# PowerBoard.net
KiCad netlist of a schematic drawn in Altium Designer
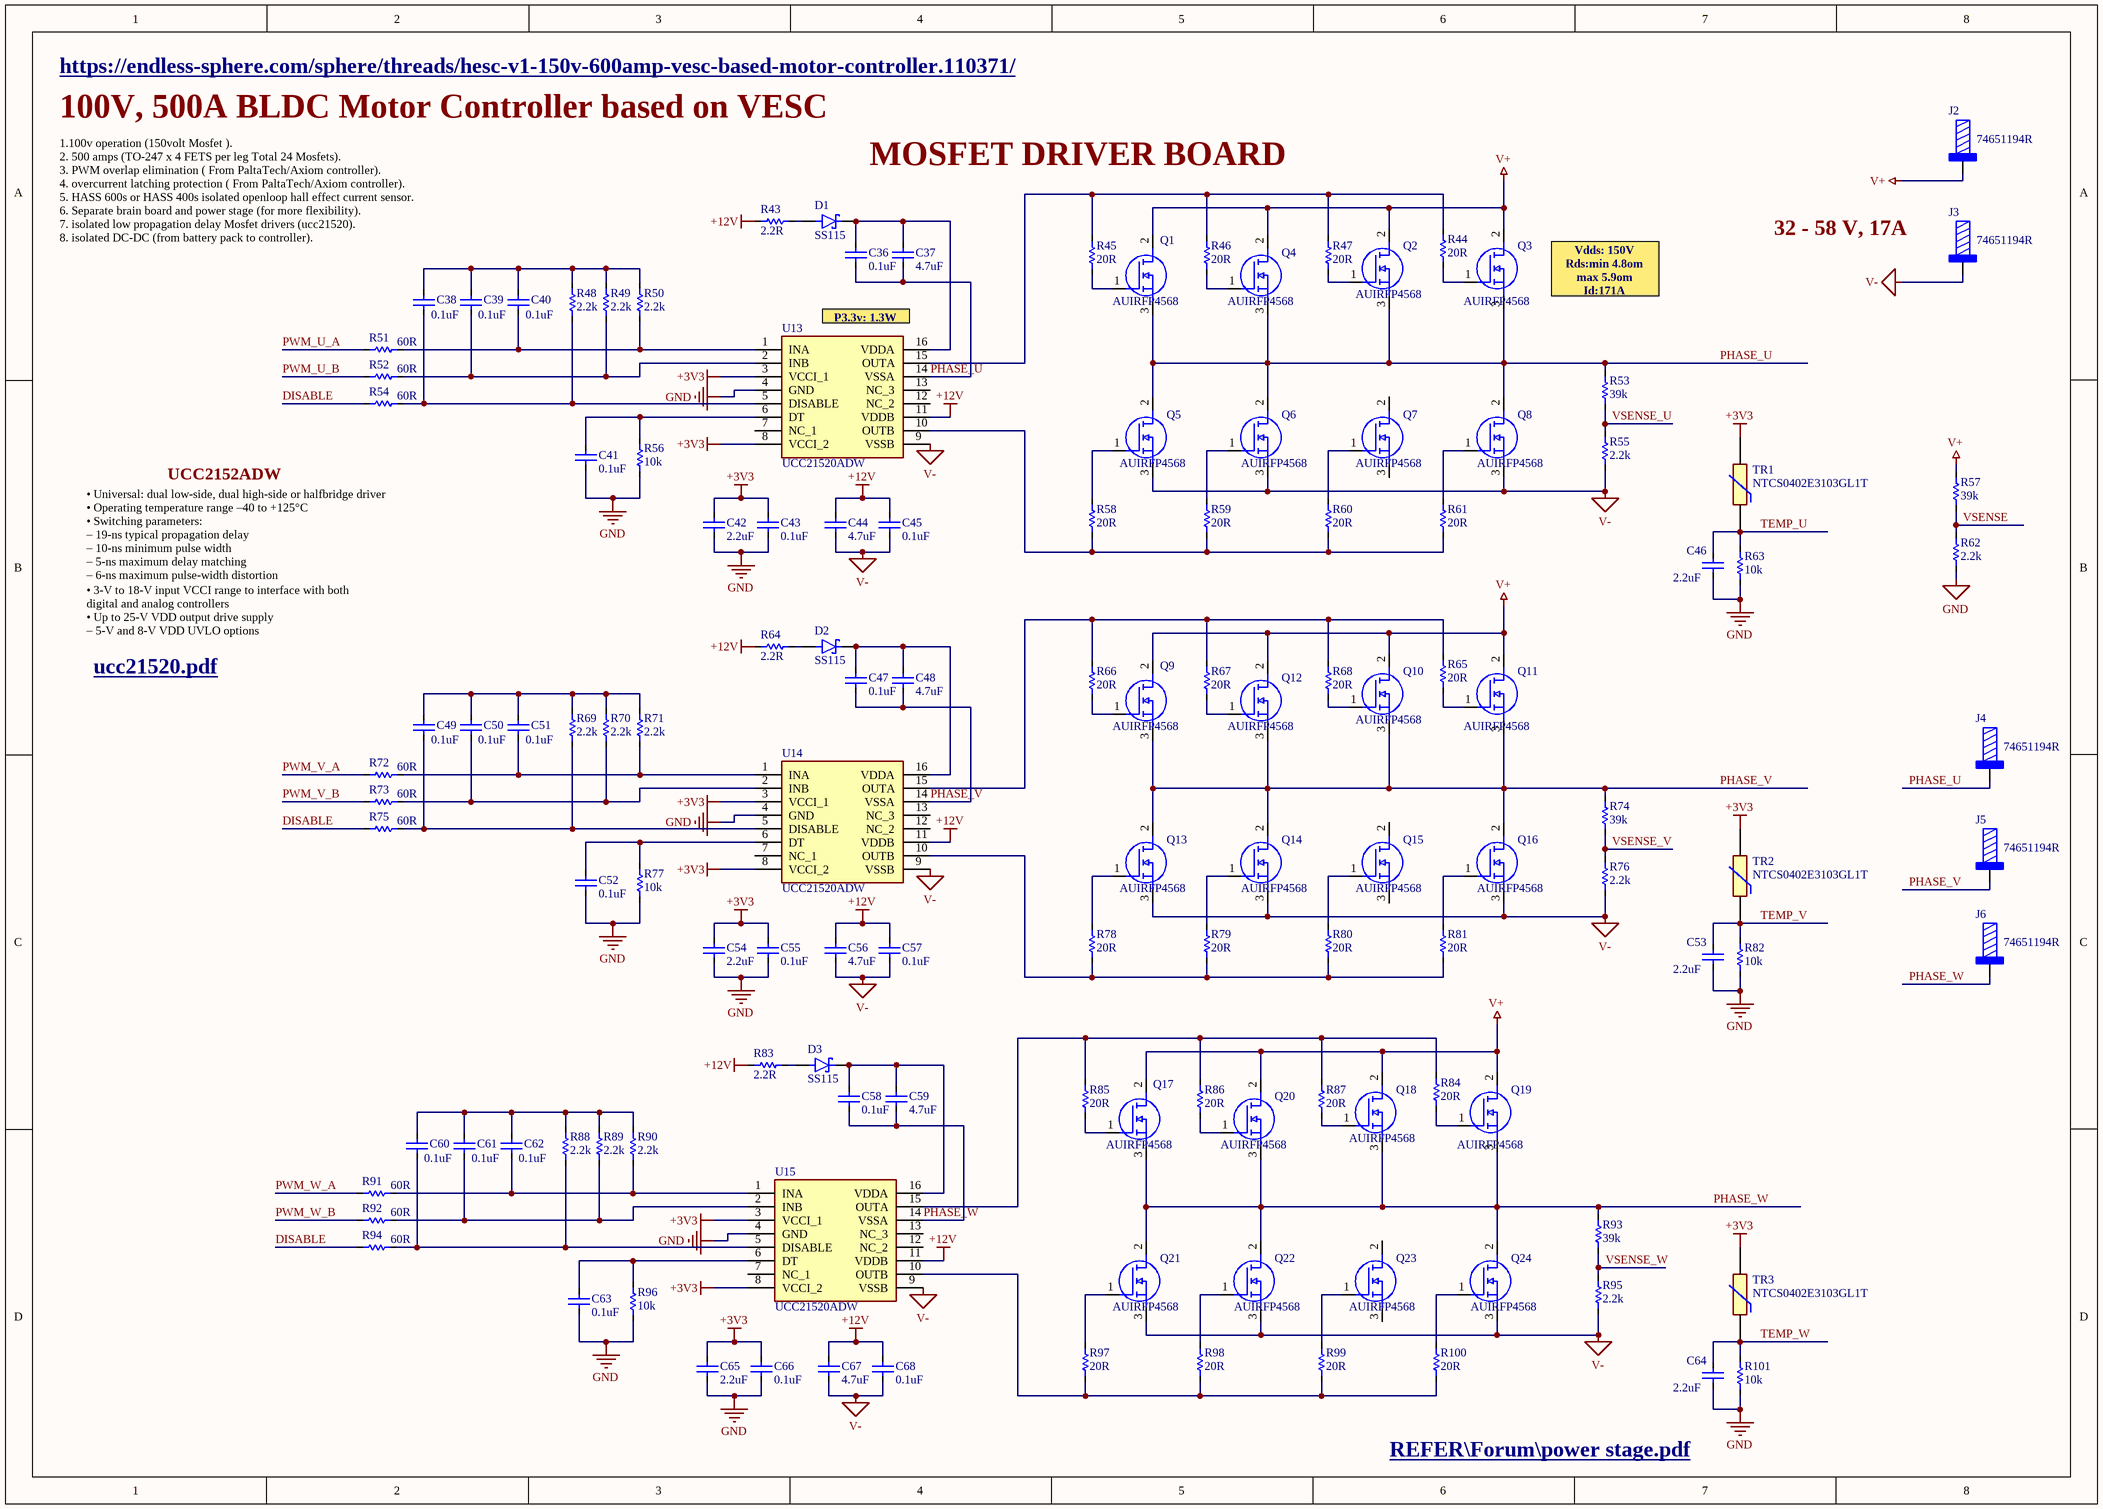
[diagram p0: PowerBoard.SchDoc]

(export (version "E")
  (design (tool "Eeschema 10.0.6"))
  (components
    (comp (ref "C36")
      (value "0.1uF")
      (footprint "SMD_C(0402)")
      (description "Multilayer Ceramic Capacitors MLCC - SMD/SMT 50 V 0.1uF X7R 0603 10%")
      (fields
        (field (name "MANUFACTURER") "Yageo")
        (field (name "MANUFACTURER PART NUMBER") "CC0603KPX7R9BB104")
      )
      (libsource (lib "CameraBoard") (part "Cap_1"))
    )
    (comp (ref "C37")
      (value "4.7uF")
      (footprint "SMD_C(0603)")
      (description "PHE840MA6100MA04R17")
      (fields
        (field (name "MANUFACTURER") "Yageo")
        (field (name "MANUFACTURER PART NUMBER") "CC0603KPX7R9BB104")
      )
      (libsource (lib "CameraBoard") (part "Cap_10"))
    )
    (comp (ref "C38")
      (value "0.1uF")
      (footprint "SMD_C(0402)")
      (description "Multilayer Ceramic Capacitors MLCC - SMD/SMT 50 V 0.1uF X7R 0603 10%")
      (fields
        (field (name "MANUFACTURER") "Yageo")
        (field (name "MANUFACTURER PART NUMBER") "CC0603KPX7R9BB104")
      )
      (libsource (lib "CameraBoard") (part "Cap_1"))
    )
    (comp (ref "C39")
      (value "0.1uF")
      (footprint "SMD_C(0402)")
      (description "Multilayer Ceramic Capacitors MLCC - SMD/SMT 50 V 0.1uF X7R 0603 10%")
      (fields
        (field (name "MANUFACTURER") "Yageo")
        (field (name "MANUFACTURER PART NUMBER") "CC0603KPX7R9BB104")
      )
      (libsource (lib "CameraBoard") (part "Cap_1"))
    )
    (comp (ref "C40")
      (value "0.1uF")
      (footprint "SMD_C(0402)")
      (description "Multilayer Ceramic Capacitors MLCC - SMD/SMT 50 V 0.1uF X7R 0603 10%")
      (fields
        (field (name "MANUFACTURER") "Yageo")
        (field (name "MANUFACTURER PART NUMBER") "CC0603KPX7R9BB104")
      )
      (libsource (lib "CameraBoard") (part "Cap_1"))
    )
    (comp (ref "C41")
      (value "0.1uF")
      (footprint "SMD_C(0402)")
      (description "Multilayer Ceramic Capacitors MLCC - SMD/SMT 50 V 0.1uF X7R 0603 10%")
      (fields
        (field (name "MANUFACTURER") "Yageo")
        (field (name "MANUFACTURER PART NUMBER") "CC0603KPX7R9BB104")
      )
      (libsource (lib "CameraBoard") (part "Cap_1"))
    )
    (comp (ref "C42")
      (value "2.2uF")
      (footprint "SMD_C(0603)")
      (description "PHE840MA6100MA04R17")
      (fields
        (field (name "MANUFACTURER") "Yageo")
        (field (name "MANUFACTURER PART NUMBER") "CC0603KPX7R9BB104")
      )
      (libsource (lib "CameraBoard") (part "Cap_10"))
    )
    (comp (ref "C43")
      (value "0.1uF")
      (footprint "SMD_C(0402)")
      (description "Multilayer Ceramic Capacitors MLCC - SMD/SMT 50 V 0.1uF X7R 0603 10%")
      (fields
        (field (name "MANUFACTURER") "Yageo")
        (field (name "MANUFACTURER PART NUMBER") "CC0603KPX7R9BB104")
      )
      (libsource (lib "CameraBoard") (part "Cap_1"))
    )
    (comp (ref "C44")
      (value "4.7uF")
      (footprint "SMD_C(0603)")
      (description "PHE840MA6100MA04R17")
      (fields
        (field (name "MANUFACTURER") "Yageo")
        (field (name "MANUFACTURER PART NUMBER") "CC0603KPX7R9BB104")
      )
      (libsource (lib "CameraBoard") (part "Cap_10"))
    )
    (comp (ref "C45")
      (value "0.1uF")
      (footprint "SMD_C(0402)")
      (description "Multilayer Ceramic Capacitors MLCC - SMD/SMT 50 V 0.1uF X7R 0603 10%")
      (fields
        (field (name "MANUFACTURER") "Yageo")
        (field (name "MANUFACTURER PART NUMBER") "CC0603KPX7R9BB104")
      )
      (libsource (lib "CameraBoard") (part "Cap_1"))
    )
    (comp (ref "C46")
      (value "2.2uF")
      (footprint "SMD_C(0402)")
      (description "Multilayer Ceramic Capacitors MLCC - SMD/SMT 50 V 0.1uF X7R 0603 10%")
      (libsource (lib "CameraBoard") (part "Cap_1"))
    )
    (comp (ref "C47")
      (value "0.1uF")
      (footprint "SMD_C(0402)")
      (description "Multilayer Ceramic Capacitors MLCC - SMD/SMT 50 V 0.1uF X7R 0603 10%")
      (fields
        (field (name "MANUFACTURER") "Yageo")
        (field (name "MANUFACTURER PART NUMBER") "CC0603KPX7R9BB104")
      )
      (libsource (lib "CameraBoard") (part "Cap_1"))
    )
    (comp (ref "C48")
      (value "4.7uF")
      (footprint "SMD_C(0603)")
      (description "PHE840MA6100MA04R17")
      (fields
        (field (name "MANUFACTURER") "Yageo")
        (field (name "MANUFACTURER PART NUMBER") "CC0603KPX7R9BB104")
      )
      (libsource (lib "CameraBoard") (part "Cap_10"))
    )
    (comp (ref "C49")
      (value "0.1uF")
      (footprint "SMD_C(0402)")
      (description "Multilayer Ceramic Capacitors MLCC - SMD/SMT 50 V 0.1uF X7R 0603 10%")
      (fields
        (field (name "MANUFACTURER") "Yageo")
        (field (name "MANUFACTURER PART NUMBER") "CC0603KPX7R9BB104")
      )
      (libsource (lib "CameraBoard") (part "Cap_1"))
    )
    (comp (ref "C50")
      (value "0.1uF")
      (footprint "SMD_C(0402)")
      (description "Multilayer Ceramic Capacitors MLCC - SMD/SMT 50 V 0.1uF X7R 0603 10%")
      (fields
        (field (name "MANUFACTURER") "Yageo")
        (field (name "MANUFACTURER PART NUMBER") "CC0603KPX7R9BB104")
      )
      (libsource (lib "CameraBoard") (part "Cap_1"))
    )
    (comp (ref "C51")
      (value "0.1uF")
      (footprint "SMD_C(0402)")
      (description "Multilayer Ceramic Capacitors MLCC - SMD/SMT 50 V 0.1uF X7R 0603 10%")
      (fields
        (field (name "MANUFACTURER") "Yageo")
        (field (name "MANUFACTURER PART NUMBER") "CC0603KPX7R9BB104")
      )
      (libsource (lib "CameraBoard") (part "Cap_1"))
    )
    (comp (ref "C52")
      (value "0.1uF")
      (footprint "SMD_C(0402)")
      (description "Multilayer Ceramic Capacitors MLCC - SMD/SMT 50 V 0.1uF X7R 0603 10%")
      (fields
        (field (name "MANUFACTURER") "Yageo")
        (field (name "MANUFACTURER PART NUMBER") "CC0603KPX7R9BB104")
      )
      (libsource (lib "CameraBoard") (part "Cap_1"))
    )
    (comp (ref "C53")
      (value "2.2uF")
      (footprint "SMD_C(0402)")
      (description "Multilayer Ceramic Capacitors MLCC - SMD/SMT 50 V 0.1uF X7R 0603 10%")
      (libsource (lib "CameraBoard") (part "Cap_1"))
    )
    (comp (ref "C54")
      (value "2.2uF")
      (footprint "SMD_C(0603)")
      (description "PHE840MA6100MA04R17")
      (fields
        (field (name "MANUFACTURER") "Yageo")
        (field (name "MANUFACTURER PART NUMBER") "CC0603KPX7R9BB104")
      )
      (libsource (lib "CameraBoard") (part "Cap_10"))
    )
    (comp (ref "C55")
      (value "0.1uF")
      (footprint "SMD_C(0402)")
      (description "Multilayer Ceramic Capacitors MLCC - SMD/SMT 50 V 0.1uF X7R 0603 10%")
      (fields
        (field (name "MANUFACTURER") "Yageo")
        (field (name "MANUFACTURER PART NUMBER") "CC0603KPX7R9BB104")
      )
      (libsource (lib "CameraBoard") (part "Cap_1"))
    )
    (comp (ref "C56")
      (value "4.7uF")
      (footprint "SMD_C(0603)")
      (description "PHE840MA6100MA04R17")
      (fields
        (field (name "MANUFACTURER") "Yageo")
        (field (name "MANUFACTURER PART NUMBER") "CC0603KPX7R9BB104")
      )
      (libsource (lib "CameraBoard") (part "Cap_10"))
    )
    (comp (ref "C57")
      (value "0.1uF")
      (footprint "SMD_C(0402)")
      (description "Multilayer Ceramic Capacitors MLCC - SMD/SMT 50 V 0.1uF X7R 0603 10%")
      (fields
        (field (name "MANUFACTURER") "Yageo")
        (field (name "MANUFACTURER PART NUMBER") "CC0603KPX7R9BB104")
      )
      (libsource (lib "CameraBoard") (part "Cap_1"))
    )
    (comp (ref "C58")
      (value "0.1uF")
      (footprint "SMD_C(0402)")
      (description "Multilayer Ceramic Capacitors MLCC - SMD/SMT 50 V 0.1uF X7R 0603 10%")
      (fields
        (field (name "MANUFACTURER") "Yageo")
        (field (name "MANUFACTURER PART NUMBER") "CC0603KPX7R9BB104")
      )
      (libsource (lib "CameraBoard") (part "Cap_1"))
    )
    (comp (ref "C59")
      (value "4.7uF")
      (footprint "SMD_C(0603)")
      (description "PHE840MA6100MA04R17")
      (fields
        (field (name "MANUFACTURER") "Yageo")
        (field (name "MANUFACTURER PART NUMBER") "CC0603KPX7R9BB104")
      )
      (libsource (lib "CameraBoard") (part "Cap_10"))
    )
    (comp (ref "C60")
      (value "0.1uF")
      (footprint "SMD_C(0402)")
      (description "Multilayer Ceramic Capacitors MLCC - SMD/SMT 50 V 0.1uF X7R 0603 10%")
      (fields
        (field (name "MANUFACTURER") "Yageo")
        (field (name "MANUFACTURER PART NUMBER") "CC0603KPX7R9BB104")
      )
      (libsource (lib "CameraBoard") (part "Cap_1"))
    )
    (comp (ref "C61")
      (value "0.1uF")
      (footprint "SMD_C(0402)")
      (description "Multilayer Ceramic Capacitors MLCC - SMD/SMT 50 V 0.1uF X7R 0603 10%")
      (fields
        (field (name "MANUFACTURER") "Yageo")
        (field (name "MANUFACTURER PART NUMBER") "CC0603KPX7R9BB104")
      )
      (libsource (lib "CameraBoard") (part "Cap_1"))
    )
    (comp (ref "C62")
      (value "0.1uF")
      (footprint "SMD_C(0402)")
      (description "Multilayer Ceramic Capacitors MLCC - SMD/SMT 50 V 0.1uF X7R 0603 10%")
      (fields
        (field (name "MANUFACTURER") "Yageo")
        (field (name "MANUFACTURER PART NUMBER") "CC0603KPX7R9BB104")
      )
      (libsource (lib "CameraBoard") (part "Cap_1"))
    )
    (comp (ref "C63")
      (value "0.1uF")
      (footprint "SMD_C(0402)")
      (description "Multilayer Ceramic Capacitors MLCC - SMD/SMT 50 V 0.1uF X7R 0603 10%")
      (fields
        (field (name "MANUFACTURER") "Yageo")
        (field (name "MANUFACTURER PART NUMBER") "CC0603KPX7R9BB104")
      )
      (libsource (lib "CameraBoard") (part "Cap_1"))
    )
    (comp (ref "C64")
      (value "2.2uF")
      (footprint "SMD_C(0402)")
      (description "Multilayer Ceramic Capacitors MLCC - SMD/SMT 50 V 0.1uF X7R 0603 10%")
      (libsource (lib "CameraBoard") (part "Cap_1"))
    )
    (comp (ref "C65")
      (value "2.2uF")
      (footprint "SMD_C(0603)")
      (description "PHE840MA6100MA04R17")
      (fields
        (field (name "MANUFACTURER") "Yageo")
        (field (name "MANUFACTURER PART NUMBER") "CC0603KPX7R9BB104")
      )
      (libsource (lib "CameraBoard") (part "Cap_10"))
    )
    (comp (ref "C66")
      (value "0.1uF")
      (footprint "SMD_C(0402)")
      (description "Multilayer Ceramic Capacitors MLCC - SMD/SMT 50 V 0.1uF X7R 0603 10%")
      (fields
        (field (name "MANUFACTURER") "Yageo")
        (field (name "MANUFACTURER PART NUMBER") "CC0603KPX7R9BB104")
      )
      (libsource (lib "CameraBoard") (part "Cap_1"))
    )
    (comp (ref "C67")
      (value "4.7uF")
      (footprint "SMD_C(0603)")
      (description "PHE840MA6100MA04R17")
      (fields
        (field (name "MANUFACTURER") "Yageo")
        (field (name "MANUFACTURER PART NUMBER") "CC0603KPX7R9BB104")
      )
      (libsource (lib "CameraBoard") (part "Cap_10"))
    )
    (comp (ref "C68")
      (value "0.1uF")
      (footprint "SMD_C(0402)")
      (description "Multilayer Ceramic Capacitors MLCC - SMD/SMT 50 V 0.1uF X7R 0603 10%")
      (fields
        (field (name "MANUFACTURER") "Yageo")
        (field (name "MANUFACTURER PART NUMBER") "CC0603KPX7R9BB104")
      )
      (libsource (lib "CameraBoard") (part "Cap_1"))
    )
    (comp (ref "D1")
      (value "SS115")
      (footprint "DIOM4325X250N")
      (description "1A, 150V, Schottky Rectifier")
      (fields (field (name "MF") "Taiwan Semiconductor"))
      (libsource (lib "SS115") (part "SS115"))
    )
    (comp (ref "D2")
      (value "SS115")
      (footprint "DIOM4325X250N")
      (description "1A, 150V, Schottky Rectifier")
      (fields (field (name "MF") "Taiwan Semiconductor"))
      (libsource (lib "SS115") (part "SS115"))
    )
    (comp (ref "D3")
      (value "SS115")
      (footprint "DIOM4325X250N")
      (description "1A, 150V, Schottky Rectifier")
      (fields (field (name "MF") "Taiwan Semiconductor"))
      (libsource (lib "SS115") (part "SS115"))
    )
    (comp (ref "J2")
      (value "74651194R")
      (footprint "74651194")
      (description "WP-THRSH REDCUBE THR with external thread, M4 x 5mm, 85A")
      (fields (field (name "MANUFACTURER") "Wurth Elektronik"))
      (libsource (lib "WP-THRSH") (part "74651194R"))
    )
    (comp (ref "J3")
      (value "74651194R")
      (footprint "74651194")
      (description "WP-THRSH REDCUBE THR with external thread, M4 x 5mm, 85A")
      (fields (field (name "MANUFACTURER") "Wurth Elektronik"))
      (libsource (lib "WP-THRSH") (part "74651194R"))
    )
    (comp (ref "J4")
      (value "74651194R")
      (footprint "74651194")
      (description "WP-THRSH REDCUBE THR with external thread, M4 x 5mm, 85A")
      (fields (field (name "MANUFACTURER") "Wurth Elektronik"))
      (libsource (lib "WP-THRSH") (part "74651194R"))
    )
    (comp (ref "J5")
      (value "74651194R")
      (footprint "74651194")
      (description "WP-THRSH REDCUBE THR with external thread, M4 x 5mm, 85A")
      (fields (field (name "MANUFACTURER") "Wurth Elektronik"))
      (libsource (lib "WP-THRSH") (part "74651194R"))
    )
    (comp (ref "J6")
      (value "74651194R")
      (footprint "74651194")
      (description "WP-THRSH REDCUBE THR with external thread, M4 x 5mm, 85A")
      (fields (field (name "MANUFACTURER") "Wurth Elektronik"))
      (libsource (lib "WP-THRSH") (part "74651194R"))
    )
    (comp (ref "Q1")
      (value "AUIRFP4568")
      (footprint "TO546P531X1558X2499-3P")
      (description "MOSFET N-CHANNEL 100+")
      (fields (field (name "MOUSER PART NUMBER") "942-AUIRFP4568"))
      (libsource (lib "AUIRFP4568") (part "AUIRFP4568"))
    )
    (comp (ref "Q2")
      (value "AUIRFP4568")
      (footprint "TO546P531X1558X2499-3P")
      (description "MOSFET N-CHANNEL 100+")
      (fields (field (name "MOUSER PART NUMBER") "942-AUIRFP4568"))
      (libsource (lib "AUIRFP4568") (part "AUIRFP4568"))
    )
    (comp (ref "Q3")
      (value "AUIRFP4568")
      (footprint "TO546P531X1558X2499-3P")
      (description "MOSFET N-CHANNEL 100+")
      (fields (field (name "MOUSER PART NUMBER") "942-AUIRFP4568"))
      (libsource (lib "AUIRFP4568") (part "AUIRFP4568"))
    )
    (comp (ref "Q4")
      (value "AUIRFP4568")
      (footprint "TO546P531X1558X2499-3P")
      (description "MOSFET N-CHANNEL 100+")
      (fields (field (name "MOUSER PART NUMBER") "942-AUIRFP4568"))
      (libsource (lib "AUIRFP4568") (part "AUIRFP4568"))
    )
    (comp (ref "Q5")
      (value "AUIRFP4568")
      (footprint "TO546P531X1558X2499-3P")
      (description "MOSFET N-CHANNEL 100+")
      (fields (field (name "MOUSER PART NUMBER") "942-AUIRFP4568"))
      (libsource (lib "AUIRFP4568") (part "AUIRFP4568"))
    )
    (comp (ref "Q6")
      (value "AUIRFP4568")
      (footprint "TO546P531X1558X2499-3P")
      (description "MOSFET N-CHANNEL 100+")
      (fields (field (name "MOUSER PART NUMBER") "942-AUIRFP4568"))
      (libsource (lib "AUIRFP4568") (part "AUIRFP4568"))
    )
    (comp (ref "Q7")
      (value "AUIRFP4568")
      (footprint "TO546P531X1558X2499-3P")
      (description "MOSFET N-CHANNEL 100+")
      (fields (field (name "MOUSER PART NUMBER") "942-AUIRFP4568"))
      (libsource (lib "AUIRFP4568") (part "AUIRFP4568"))
    )
    (comp (ref "Q8")
      (value "AUIRFP4568")
      (footprint "TO546P531X1558X2499-3P")
      (description "MOSFET N-CHANNEL 100+")
      (fields (field (name "MOUSER PART NUMBER") "942-AUIRFP4568"))
      (libsource (lib "AUIRFP4568") (part "AUIRFP4568"))
    )
    (comp (ref "Q9")
      (value "AUIRFP4568")
      (footprint "TO546P531X1558X2499-3P")
      (description "MOSFET N-CHANNEL 100+")
      (fields (field (name "MOUSER PART NUMBER") "942-AUIRFP4568"))
      (libsource (lib "AUIRFP4568") (part "AUIRFP4568"))
    )
    (comp (ref "Q10")
      (value "AUIRFP4568")
      (footprint "TO546P531X1558X2499-3P")
      (description "MOSFET N-CHANNEL 100+")
      (fields (field (name "MOUSER PART NUMBER") "942-AUIRFP4568"))
      (libsource (lib "AUIRFP4568") (part "AUIRFP4568"))
    )
    (comp (ref "Q11")
      (value "AUIRFP4568")
      (footprint "TO546P531X1558X2499-3P")
      (description "MOSFET N-CHANNEL 100+")
      (fields (field (name "MOUSER PART NUMBER") "942-AUIRFP4568"))
      (libsource (lib "AUIRFP4568") (part "AUIRFP4568"))
    )
    (comp (ref "Q12")
      (value "AUIRFP4568")
      (footprint "TO546P531X1558X2499-3P")
      (description "MOSFET N-CHANNEL 100+")
      (fields (field (name "MOUSER PART NUMBER") "942-AUIRFP4568"))
      (libsource (lib "AUIRFP4568") (part "AUIRFP4568"))
    )
    (comp (ref "Q13")
      (value "AUIRFP4568")
      (footprint "TO546P531X1558X2499-3P")
      (description "MOSFET N-CHANNEL 100+")
      (fields (field (name "MOUSER PART NUMBER") "942-AUIRFP4568"))
      (libsource (lib "AUIRFP4568") (part "AUIRFP4568"))
    )
    (comp (ref "Q14")
      (value "AUIRFP4568")
      (footprint "TO546P531X1558X2499-3P")
      (description "MOSFET N-CHANNEL 100+")
      (fields (field (name "MOUSER PART NUMBER") "942-AUIRFP4568"))
      (libsource (lib "AUIRFP4568") (part "AUIRFP4568"))
    )
    (comp (ref "Q15")
      (value "AUIRFP4568")
      (footprint "TO546P531X1558X2499-3P")
      (description "MOSFET N-CHANNEL 100+")
      (fields (field (name "MOUSER PART NUMBER") "942-AUIRFP4568"))
      (libsource (lib "AUIRFP4568") (part "AUIRFP4568"))
    )
    (comp (ref "Q16")
      (value "AUIRFP4568")
      (footprint "TO546P531X1558X2499-3P")
      (description "MOSFET N-CHANNEL 100+")
      (fields (field (name "MOUSER PART NUMBER") "942-AUIRFP4568"))
      (libsource (lib "AUIRFP4568") (part "AUIRFP4568"))
    )
    (comp (ref "Q17")
      (value "AUIRFP4568")
      (footprint "TO546P531X1558X2499-3P")
      (description "MOSFET N-CHANNEL 100+")
      (fields (field (name "MOUSER PART NUMBER") "942-AUIRFP4568"))
      (libsource (lib "AUIRFP4568") (part "AUIRFP4568"))
    )
    (comp (ref "Q18")
      (value "AUIRFP4568")
      (footprint "TO546P531X1558X2499-3P")
      (description "MOSFET N-CHANNEL 100+")
      (fields (field (name "MOUSER PART NUMBER") "942-AUIRFP4568"))
      (libsource (lib "AUIRFP4568") (part "AUIRFP4568"))
    )
    (comp (ref "Q19")
      (value "AUIRFP4568")
      (footprint "TO546P531X1558X2499-3P")
      (description "MOSFET N-CHANNEL 100+")
      (fields (field (name "MOUSER PART NUMBER") "942-AUIRFP4568"))
      (libsource (lib "AUIRFP4568") (part "AUIRFP4568"))
    )
    (comp (ref "Q20")
      (value "AUIRFP4568")
      (footprint "TO546P531X1558X2499-3P")
      (description "MOSFET N-CHANNEL 100+")
      (fields (field (name "MOUSER PART NUMBER") "942-AUIRFP4568"))
      (libsource (lib "AUIRFP4568") (part "AUIRFP4568"))
    )
    (comp (ref "Q21")
      (value "AUIRFP4568")
      (footprint "TO546P531X1558X2499-3P")
      (description "MOSFET N-CHANNEL 100+")
      (fields (field (name "MOUSER PART NUMBER") "942-AUIRFP4568"))
      (libsource (lib "AUIRFP4568") (part "AUIRFP4568"))
    )
    (comp (ref "Q22")
      (value "AUIRFP4568")
      (footprint "TO546P531X1558X2499-3P")
      (description "MOSFET N-CHANNEL 100+")
      (fields (field (name "MOUSER PART NUMBER") "942-AUIRFP4568"))
      (libsource (lib "AUIRFP4568") (part "AUIRFP4568"))
    )
    (comp (ref "Q23")
      (value "AUIRFP4568")
      (footprint "TO546P531X1558X2499-3P")
      (description "MOSFET N-CHANNEL 100+")
      (fields (field (name "MOUSER PART NUMBER") "942-AUIRFP4568"))
      (libsource (lib "AUIRFP4568") (part "AUIRFP4568"))
    )
    (comp (ref "Q24")
      (value "AUIRFP4568")
      (footprint "TO546P531X1558X2499-3P")
      (description "MOSFET N-CHANNEL 100+")
      (fields (field (name "MOUSER PART NUMBER") "942-AUIRFP4568"))
      (libsource (lib "AUIRFP4568") (part "AUIRFP4568"))
    )
    (comp (ref "R43")
      (value "2.2R")
      (footprint "SMD_R(0402)")
      (description "CRCW04024R02FKED")
      (fields (field (name "PUBLISHER") "Altium Limited"))
      (libsource (lib "CameraBoard") (part "Res Semi_1"))
    )
    (comp (ref "R44")
      (value "20R")
      (footprint "SMD_R(0402)")
      (description "CRCW04024R02FKED")
      (fields (field (name "PUBLISHER") "Altium Limited"))
      (libsource (lib "CameraBoard") (part "Res Semi_1"))
    )
    (comp (ref "R45")
      (value "20R")
      (footprint "SMD_R(0402)")
      (description "CRCW04024R02FKED")
      (fields (field (name "PUBLISHER") "Altium Limited"))
      (libsource (lib "CameraBoard") (part "Res Semi_1"))
    )
    (comp (ref "R46")
      (value "20R")
      (footprint "SMD_R(0402)")
      (description "CRCW04024R02FKED")
      (fields (field (name "PUBLISHER") "Altium Limited"))
      (libsource (lib "CameraBoard") (part "Res Semi_1"))
    )
    (comp (ref "R47")
      (value "20R")
      (footprint "SMD_R(0402)")
      (description "CRCW04024R02FKED")
      (fields (field (name "PUBLISHER") "Altium Limited"))
      (libsource (lib "CameraBoard") (part "Res Semi_1"))
    )
    (comp (ref "R48")
      (value "2.2k")
      (footprint "SMD_R(0402)")
      (description "CRCW04024R02FKED")
      (fields (field (name "PUBLISHER") "Altium Limited"))
      (libsource (lib "CameraBoard") (part "Res Semi_2"))
    )
    (comp (ref "R49")
      (value "2.2k")
      (footprint "SMD_R(0402)")
      (description "CRCW04024R02FKED")
      (fields (field (name "PUBLISHER") "Altium Limited"))
      (libsource (lib "CameraBoard") (part "Res Semi_2"))
    )
    (comp (ref "R50")
      (value "2.2k")
      (footprint "SMD_R(0402)")
      (description "CRCW04024R02FKED")
      (fields (field (name "PUBLISHER") "Altium Limited"))
      (libsource (lib "CameraBoard") (part "Res Semi_2"))
    )
    (comp (ref "R51")
      (value "60R")
      (footprint "SMD_R(0402)")
      (description "CRCW04024R02FKED")
      (fields (field (name "PUBLISHER") "Altium Limited"))
      (libsource (lib "CameraBoard") (part "Res Semi_1"))
    )
    (comp (ref "R52")
      (value "60R")
      (footprint "SMD_R(0402)")
      (description "CRCW04024R02FKED")
      (fields (field (name "PUBLISHER") "Altium Limited"))
      (libsource (lib "CameraBoard") (part "Res Semi_1"))
    )
    (comp (ref "R53")
      (value "39k")
      (footprint "SMD_R(0402)")
      (description "CRCW04024R02FKED")
      (fields (field (name "PUBLISHER") "Altium Limited"))
      (libsource (lib "CameraBoard") (part "Res Semi_5"))
    )
    (comp (ref "R54")
      (value "60R")
      (footprint "SMD_R(0402)")
      (description "CRCW04024R02FKED")
      (fields (field (name "PUBLISHER") "Altium Limited"))
      (libsource (lib "CameraBoard") (part "Res Semi_1"))
    )
    (comp (ref "R55")
      (value "2.2k")
      (footprint "SMD_R(0402)")
      (description "CRCW04024R02FKED")
      (fields (field (name "PUBLISHER") "Altium Limited"))
      (libsource (lib "CameraBoard") (part "Res Semi_5"))
    )
    (comp (ref "R56")
      (value "10k")
      (footprint "SMD_R(0402)")
      (description "CRCW04024R02FKED")
      (fields (field (name "PUBLISHER") "Altium Limited"))
      (libsource (lib "CameraBoard") (part "Res Semi_5"))
    )
    (comp (ref "R57")
      (value "39k")
      (footprint "SMD_R(0402)")
      (description "CRCW04024R02FKED")
      (fields (field (name "PUBLISHER") "Altium Limited"))
      (libsource (lib "CameraBoard") (part "Res Semi_5"))
    )
    (comp (ref "R58")
      (value "20R")
      (footprint "SMD_R(0402)")
      (description "CRCW04024R02FKED")
      (fields (field (name "PUBLISHER") "Altium Limited"))
      (libsource (lib "CameraBoard") (part "Res Semi_1"))
    )
    (comp (ref "R59")
      (value "20R")
      (footprint "SMD_R(0402)")
      (description "CRCW04024R02FKED")
      (fields (field (name "PUBLISHER") "Altium Limited"))
      (libsource (lib "CameraBoard") (part "Res Semi_1"))
    )
    (comp (ref "R60")
      (value "20R")
      (footprint "SMD_R(0402)")
      (description "CRCW04024R02FKED")
      (fields (field (name "PUBLISHER") "Altium Limited"))
      (libsource (lib "CameraBoard") (part "Res Semi_1"))
    )
    (comp (ref "R61")
      (value "20R")
      (footprint "SMD_R(0402)")
      (description "CRCW04024R02FKED")
      (fields (field (name "PUBLISHER") "Altium Limited"))
      (libsource (lib "CameraBoard") (part "Res Semi_1"))
    )
    (comp (ref "R62")
      (value "2.2k")
      (footprint "SMD_R(0402)")
      (description "CRCW04024R02FKED")
      (fields (field (name "PUBLISHER") "Altium Limited"))
      (libsource (lib "CameraBoard") (part "Res Semi_5"))
    )
    (comp (ref "R63")
      (value "10k")
      (footprint "SMD_R(0402)")
      (description "CRCW04024R02FKED")
      (fields (field (name "PUBLISHER") "Altium Limited"))
      (libsource (lib "CameraBoard") (part "Res Semi_5"))
    )
    (comp (ref "R64")
      (value "2.2R")
      (footprint "SMD_R(0402)")
      (description "CRCW04024R02FKED")
      (fields (field (name "PUBLISHER") "Altium Limited"))
      (libsource (lib "CameraBoard") (part "Res Semi_1"))
    )
    (comp (ref "R65")
      (value "20R")
      (footprint "SMD_R(0402)")
      (description "CRCW04024R02FKED")
      (fields (field (name "PUBLISHER") "Altium Limited"))
      (libsource (lib "CameraBoard") (part "Res Semi_1"))
    )
    (comp (ref "R66")
      (value "20R")
      (footprint "SMD_R(0402)")
      (description "CRCW04024R02FKED")
      (fields (field (name "PUBLISHER") "Altium Limited"))
      (libsource (lib "CameraBoard") (part "Res Semi_1"))
    )
    (comp (ref "R67")
      (value "20R")
      (footprint "SMD_R(0402)")
      (description "CRCW04024R02FKED")
      (fields (field (name "PUBLISHER") "Altium Limited"))
      (libsource (lib "CameraBoard") (part "Res Semi_1"))
    )
    (comp (ref "R68")
      (value "20R")
      (footprint "SMD_R(0402)")
      (description "CRCW04024R02FKED")
      (fields (field (name "PUBLISHER") "Altium Limited"))
      (libsource (lib "CameraBoard") (part "Res Semi_1"))
    )
    (comp (ref "R69")
      (value "2.2k")
      (footprint "SMD_R(0402)")
      (description "CRCW04024R02FKED")
      (fields (field (name "PUBLISHER") "Altium Limited"))
      (libsource (lib "CameraBoard") (part "Res Semi_2"))
    )
    (comp (ref "R70")
      (value "2.2k")
      (footprint "SMD_R(0402)")
      (description "CRCW04024R02FKED")
      (fields (field (name "PUBLISHER") "Altium Limited"))
      (libsource (lib "CameraBoard") (part "Res Semi_2"))
    )
    (comp (ref "R71")
      (value "2.2k")
      (footprint "SMD_R(0402)")
      (description "CRCW04024R02FKED")
      (fields (field (name "PUBLISHER") "Altium Limited"))
      (libsource (lib "CameraBoard") (part "Res Semi_2"))
    )
    (comp (ref "R72")
      (value "60R")
      (footprint "SMD_R(0402)")
      (description "CRCW04024R02FKED")
      (fields (field (name "PUBLISHER") "Altium Limited"))
      (libsource (lib "CameraBoard") (part "Res Semi_1"))
    )
    (comp (ref "R73")
      (value "60R")
      (footprint "SMD_R(0402)")
      (description "CRCW04024R02FKED")
      (fields (field (name "PUBLISHER") "Altium Limited"))
      (libsource (lib "CameraBoard") (part "Res Semi_1"))
    )
    (comp (ref "R74")
      (value "39k")
      (footprint "SMD_R(0402)")
      (description "CRCW04024R02FKED")
      (fields (field (name "PUBLISHER") "Altium Limited"))
      (libsource (lib "CameraBoard") (part "Res Semi_5"))
    )
    (comp (ref "R75")
      (value "60R")
      (footprint "SMD_R(0402)")
      (description "CRCW04024R02FKED")
      (fields (field (name "PUBLISHER") "Altium Limited"))
      (libsource (lib "CameraBoard") (part "Res Semi_1"))
    )
    (comp (ref "R76")
      (value "2.2k")
      (footprint "SMD_R(0402)")
      (description "CRCW04024R02FKED")
      (fields (field (name "PUBLISHER") "Altium Limited"))
      (libsource (lib "CameraBoard") (part "Res Semi_5"))
    )
    (comp (ref "R77")
      (value "10k")
      (footprint "SMD_R(0402)")
      (description "CRCW04024R02FKED")
      (fields (field (name "PUBLISHER") "Altium Limited"))
      (libsource (lib "CameraBoard") (part "Res Semi_5"))
    )
    (comp (ref "R78")
      (value "20R")
      (footprint "SMD_R(0402)")
      (description "CRCW04024R02FKED")
      (fields (field (name "PUBLISHER") "Altium Limited"))
      (libsource (lib "CameraBoard") (part "Res Semi_1"))
    )
    (comp (ref "R79")
      (value "20R")
      (footprint "SMD_R(0402)")
      (description "CRCW04024R02FKED")
      (fields (field (name "PUBLISHER") "Altium Limited"))
      (libsource (lib "CameraBoard") (part "Res Semi_1"))
    )
    (comp (ref "R80")
      (value "20R")
      (footprint "SMD_R(0402)")
      (description "CRCW04024R02FKED")
      (fields (field (name "PUBLISHER") "Altium Limited"))
      (libsource (lib "CameraBoard") (part "Res Semi_1"))
    )
    (comp (ref "R81")
      (value "20R")
      (footprint "SMD_R(0402)")
      (description "CRCW04024R02FKED")
      (fields (field (name "PUBLISHER") "Altium Limited"))
      (libsource (lib "CameraBoard") (part "Res Semi_1"))
    )
    (comp (ref "R82")
      (value "10k")
      (footprint "SMD_R(0402)")
      (description "CRCW04024R02FKED")
      (fields (field (name "PUBLISHER") "Altium Limited"))
      (libsource (lib "CameraBoard") (part "Res Semi_5"))
    )
    (comp (ref "R83")
      (value "2.2R")
      (footprint "SMD_R(0402)")
      (description "CRCW04024R02FKED")
      (fields (field (name "PUBLISHER") "Altium Limited"))
      (libsource (lib "CameraBoard") (part "Res Semi_1"))
    )
    (comp (ref "R84")
      (value "20R")
      (footprint "SMD_R(0402)")
      (description "CRCW04024R02FKED")
      (fields (field (name "PUBLISHER") "Altium Limited"))
      (libsource (lib "CameraBoard") (part "Res Semi_1"))
    )
    (comp (ref "R85")
      (value "20R")
      (footprint "SMD_R(0402)")
      (description "CRCW04024R02FKED")
      (fields (field (name "PUBLISHER") "Altium Limited"))
      (libsource (lib "CameraBoard") (part "Res Semi_1"))
    )
    (comp (ref "R86")
      (value "20R")
      (footprint "SMD_R(0402)")
      (description "CRCW04024R02FKED")
      (fields (field (name "PUBLISHER") "Altium Limited"))
      (libsource (lib "CameraBoard") (part "Res Semi_1"))
    )
    (comp (ref "R87")
      (value "20R")
      (footprint "SMD_R(0402)")
      (description "CRCW04024R02FKED")
      (fields (field (name "PUBLISHER") "Altium Limited"))
      (libsource (lib "CameraBoard") (part "Res Semi_1"))
    )
    (comp (ref "R88")
      (value "2.2k")
      (footprint "SMD_R(0402)")
      (description "CRCW04024R02FKED")
      (fields (field (name "PUBLISHER") "Altium Limited"))
      (libsource (lib "CameraBoard") (part "Res Semi_2"))
    )
    (comp (ref "R89")
      (value "2.2k")
      (footprint "SMD_R(0402)")
      (description "CRCW04024R02FKED")
      (fields (field (name "PUBLISHER") "Altium Limited"))
      (libsource (lib "CameraBoard") (part "Res Semi_2"))
    )
    (comp (ref "R90")
      (value "2.2k")
      (footprint "SMD_R(0402)")
      (description "CRCW04024R02FKED")
      (fields (field (name "PUBLISHER") "Altium Limited"))
      (libsource (lib "CameraBoard") (part "Res Semi_2"))
    )
    (comp (ref "R91")
      (value "60R")
      (footprint "SMD_R(0402)")
      (description "CRCW04024R02FKED")
      (fields (field (name "PUBLISHER") "Altium Limited"))
      (libsource (lib "CameraBoard") (part "Res Semi_1"))
    )
    (comp (ref "R92")
      (value "60R")
      (footprint "SMD_R(0402)")
      (description "CRCW04024R02FKED")
      (fields (field (name "PUBLISHER") "Altium Limited"))
      (libsource (lib "CameraBoard") (part "Res Semi_1"))
    )
    (comp (ref "R93")
      (value "39k")
      (footprint "SMD_R(0402)")
      (description "CRCW04024R02FKED")
      (fields (field (name "PUBLISHER") "Altium Limited"))
      (libsource (lib "CameraBoard") (part "Res Semi_5"))
    )
    (comp (ref "R94")
      (value "60R")
      (footprint "SMD_R(0402)")
      (description "CRCW04024R02FKED")
      (fields (field (name "PUBLISHER") "Altium Limited"))
      (libsource (lib "CameraBoard") (part "Res Semi_1"))
    )
    (comp (ref "R95")
      (value "2.2k")
      (footprint "SMD_R(0402)")
      (description "CRCW04024R02FKED")
      (fields (field (name "PUBLISHER") "Altium Limited"))
      (libsource (lib "CameraBoard") (part "Res Semi_5"))
    )
    (comp (ref "R96")
      (value "10k")
      (footprint "SMD_R(0402)")
      (description "CRCW04024R02FKED")
      (fields (field (name "PUBLISHER") "Altium Limited"))
      (libsource (lib "CameraBoard") (part "Res Semi_5"))
    )
    (comp (ref "R97")
      (value "20R")
      (footprint "SMD_R(0402)")
      (description "CRCW04024R02FKED")
      (fields (field (name "PUBLISHER") "Altium Limited"))
      (libsource (lib "CameraBoard") (part "Res Semi_1"))
    )
    (comp (ref "R98")
      (value "20R")
      (footprint "SMD_R(0402)")
      (description "CRCW04024R02FKED")
      (fields (field (name "PUBLISHER") "Altium Limited"))
      (libsource (lib "CameraBoard") (part "Res Semi_1"))
    )
    (comp (ref "R99")
      (value "20R")
      (footprint "SMD_R(0402)")
      (description "CRCW04024R02FKED")
      (fields (field (name "PUBLISHER") "Altium Limited"))
      (libsource (lib "CameraBoard") (part "Res Semi_1"))
    )
    (comp (ref "R100")
      (value "20R")
      (footprint "SMD_R(0402)")
      (description "CRCW04024R02FKED")
      (fields (field (name "PUBLISHER") "Altium Limited"))
      (libsource (lib "CameraBoard") (part "Res Semi_1"))
    )
    (comp (ref "R101")
      (value "10k")
      (footprint "SMD_R(0402)")
      (description "CRCW04024R02FKED")
      (fields (field (name "PUBLISHER") "Altium Limited"))
      (libsource (lib "CameraBoard") (part "Res Semi_5"))
    )
    (comp (ref "TR1")
      (value "NTCS0402E3103GL1T")
      (footprint "THRMC1005X65N")
      (description "NTC Thermistors 10Kohms 2% AEC-Q200")
      (fields (field (name "MOUSER PART NUMBER") "594-NTCS402E3103GL1T"))
      (libsource (lib "NTCS0402E3103GL1T") (part "NTCS0402E3103GL1T"))
    )
    (comp (ref "TR2")
      (value "NTCS0402E3103GL1T")
      (footprint "THRMC1005X65N")
      (description "NTC Thermistors 10Kohms 2% AEC-Q200")
      (fields (field (name "MOUSER PART NUMBER") "594-NTCS402E3103GL1T"))
      (libsource (lib "NTCS0402E3103GL1T") (part "NTCS0402E3103GL1T"))
    )
    (comp (ref "TR3")
      (value "NTCS0402E3103GL1T")
      (footprint "THRMC1005X65N")
      (description "NTC Thermistors 10Kohms 2% AEC-Q200")
      (fields (field (name "MOUSER PART NUMBER") "594-NTCS402E3103GL1T"))
      (libsource (lib "NTCS0402E3103GL1T") (part "NTCS0402E3103GL1T"))
    )
    (comp (ref "U13")
      (value "UCC21520ADW")
      (footprint "SOIC127P1030X265-16N")
      (description "4A/6A, 5.7 kVrms Isolated Dual Channel Gate Driver")
      (fields (field (name "MOUSER PART NUMBER") "595-UCC21520ADW"))
      (libsource (lib "UCC21520ADW") (part "UCC21520ADW"))
    )
    (comp (ref "U14")
      (value "UCC21520ADW")
      (footprint "SOIC127P1030X265-16N")
      (description "4A/6A, 5.7 kVrms Isolated Dual Channel Gate Driver")
      (fields (field (name "MOUSER PART NUMBER") "595-UCC21520ADW"))
      (libsource (lib "UCC21520ADW") (part "UCC21520ADW"))
    )
    (comp (ref "U15")
      (value "UCC21520ADW")
      (footprint "SOIC127P1030X265-16N")
      (description "4A/6A, 5.7 kVrms Isolated Dual Channel Gate Driver")
      (fields (field (name "MOUSER PART NUMBER") "595-UCC21520ADW"))
      (libsource (lib "UCC21520ADW") (part "UCC21520ADW"))
    )
  )
  (nets
    (net (code "1") (name "+3V3") (class "Default")
      (node (ref "C42") (pin "2") (pinfunction "2_2") (pintype "passive"))
      (node (ref "C43") (pin "2") (pinfunction "2_2") (pintype "passive"))
      (node (ref "C54") (pin "2") (pinfunction "2_2") (pintype "passive"))
      (node (ref "C55") (pin "2") (pinfunction "2_2") (pintype "passive"))
      (node (ref "C65") (pin "2") (pinfunction "2_2") (pintype "passive"))
      (node (ref "C66") (pin "2") (pinfunction "2_2") (pintype "passive"))
      (node (ref "TR1") (pin "2") (pinfunction "2_2") (pintype "passive"))
      (node (ref "TR2") (pin "2") (pinfunction "2_2") (pintype "passive"))
      (node (ref "TR3") (pin "2") (pinfunction "2_2") (pintype "passive"))
      (node (ref "U13") (pin "3") (pinfunction "VCCI_1_3") (pintype "passive"))
      (node (ref "U13") (pin "8") (pinfunction "VCCI_2_8") (pintype "passive"))
      (node (ref "U14") (pin "3") (pinfunction "VCCI_1_3") (pintype "passive"))
      (node (ref "U14") (pin "8") (pinfunction "VCCI_2_8") (pintype "passive"))
      (node (ref "U15") (pin "3") (pinfunction "VCCI_1_3") (pintype "passive"))
      (node (ref "U15") (pin "8") (pinfunction "VCCI_2_8") (pintype "passive"))
    )
    (net (code "2") (name "+12V") (class "Default")
      (node (ref "C44") (pin "2") (pinfunction "2_2") (pintype "passive"))
      (node (ref "C45") (pin "2") (pinfunction "2_2") (pintype "passive"))
      (node (ref "C56") (pin "2") (pinfunction "2_2") (pintype "passive"))
      (node (ref "C57") (pin "2") (pinfunction "2_2") (pintype "passive"))
      (node (ref "C67") (pin "2") (pinfunction "2_2") (pintype "passive"))
      (node (ref "C68") (pin "2") (pinfunction "2_2") (pintype "passive"))
      (node (ref "R43") (pin "1") (pinfunction "1_1") (pintype "passive"))
      (node (ref "R64") (pin "1") (pinfunction "1_1") (pintype "passive"))
      (node (ref "R83") (pin "1") (pinfunction "1_1") (pintype "passive"))
      (node (ref "U13") (pin "11") (pinfunction "VDDB_11") (pintype "passive"))
      (node (ref "U14") (pin "11") (pinfunction "VDDB_11") (pintype "passive"))
      (node (ref "U15") (pin "11") (pinfunction "VDDB_11") (pintype "passive"))
    )
    (net (code "3") (name "/DISABLE") (class "Default")
      (node (ref "R54") (pin "1") (pinfunction "1_1") (pintype "passive"))
      (node (ref "R75") (pin "1") (pinfunction "1_1") (pintype "passive"))
      (node (ref "R94") (pin "1") (pinfunction "1_1") (pintype "passive"))
    )
    (net (code "4") (name "/PHASE_U") (class "Default")
      (node (ref "C36") (pin "1") (pinfunction "1_1") (pintype "passive"))
      (node (ref "C37") (pin "1") (pinfunction "1_1") (pintype "passive"))
      (node (ref "J4") (pin "1") (pinfunction "1_1") (pintype "passive"))
      (node (ref "Q1") (pin "3") (pinfunction "S_3") (pintype "passive"))
      (node (ref "Q2") (pin "3") (pinfunction "S_3") (pintype "passive"))
      (node (ref "Q3") (pin "3") (pinfunction "S_3") (pintype "passive"))
      (node (ref "Q4") (pin "3") (pinfunction "S_3") (pintype "passive"))
      (node (ref "Q5") (pin "2") (pinfunction "D_2") (pintype "passive"))
      (node (ref "Q6") (pin "2") (pinfunction "D_2") (pintype "passive"))
      (node (ref "Q8") (pin "2") (pinfunction "D_2") (pintype "passive"))
      (node (ref "R53") (pin "2") (pinfunction "2_2") (pintype "passive"))
      (node (ref "U13") (pin "14") (pinfunction "VSSA_14") (pintype "passive"))
    )
    (net (code "5") (name "/PHASE_V") (class "Default")
      (node (ref "C47") (pin "1") (pinfunction "1_1") (pintype "passive"))
      (node (ref "C48") (pin "1") (pinfunction "1_1") (pintype "passive"))
      (node (ref "J5") (pin "1") (pinfunction "1_1") (pintype "passive"))
      (node (ref "Q10") (pin "3") (pinfunction "S_3") (pintype "passive"))
      (node (ref "Q11") (pin "3") (pinfunction "S_3") (pintype "passive"))
      (node (ref "Q12") (pin "3") (pinfunction "S_3") (pintype "passive"))
      (node (ref "Q13") (pin "2") (pinfunction "D_2") (pintype "passive"))
      (node (ref "Q14") (pin "2") (pinfunction "D_2") (pintype "passive"))
      (node (ref "Q16") (pin "2") (pinfunction "D_2") (pintype "passive"))
      (node (ref "Q9") (pin "3") (pinfunction "S_3") (pintype "passive"))
      (node (ref "R74") (pin "2") (pinfunction "2_2") (pintype "passive"))
      (node (ref "U14") (pin "14") (pinfunction "VSSA_14") (pintype "passive"))
    )
    (net (code "6") (name "/PHASE_W") (class "Default")
      (node (ref "C58") (pin "1") (pinfunction "1_1") (pintype "passive"))
      (node (ref "C59") (pin "1") (pinfunction "1_1") (pintype "passive"))
      (node (ref "J6") (pin "1") (pinfunction "1_1") (pintype "passive"))
      (node (ref "Q17") (pin "3") (pinfunction "S_3") (pintype "passive"))
      (node (ref "Q18") (pin "3") (pinfunction "S_3") (pintype "passive"))
      (node (ref "Q19") (pin "3") (pinfunction "S_3") (pintype "passive"))
      (node (ref "Q20") (pin "3") (pinfunction "S_3") (pintype "passive"))
      (node (ref "Q21") (pin "2") (pinfunction "D_2") (pintype "passive"))
      (node (ref "Q22") (pin "2") (pinfunction "D_2") (pintype "passive"))
      (node (ref "Q24") (pin "2") (pinfunction "D_2") (pintype "passive"))
      (node (ref "R93") (pin "2") (pinfunction "2_2") (pintype "passive"))
      (node (ref "U15") (pin "14") (pinfunction "VSSA_14") (pintype "passive"))
    )
    (net (code "7") (name "/PWM_U_A") (class "Default")
      (node (ref "R51") (pin "1") (pinfunction "1_1") (pintype "passive"))
    )
    (net (code "8") (name "/PWM_U_B") (class "Default")
      (node (ref "R52") (pin "1") (pinfunction "1_1") (pintype "passive"))
    )
    (net (code "9") (name "/PWM_V_A") (class "Default")
      (node (ref "R72") (pin "1") (pinfunction "1_1") (pintype "passive"))
    )
    (net (code "10") (name "/PWM_V_B") (class "Default")
      (node (ref "R73") (pin "1") (pinfunction "1_1") (pintype "passive"))
    )
    (net (code "11") (name "/PWM_W_A") (class "Default")
      (node (ref "R91") (pin "1") (pinfunction "1_1") (pintype "passive"))
    )
    (net (code "12") (name "/PWM_W_B") (class "Default")
      (node (ref "R92") (pin "1") (pinfunction "1_1") (pintype "passive"))
    )
    (net (code "13") (name "/TEMP_U") (class "Default")
      (node (ref "C46") (pin "2") (pinfunction "2_2") (pintype "passive"))
      (node (ref "R63") (pin "2") (pinfunction "2_2") (pintype "passive"))
      (node (ref "TR1") (pin "1") (pinfunction "1_1") (pintype "passive"))
    )
    (net (code "14") (name "/TEMP_V") (class "Default")
      (node (ref "C53") (pin "2") (pinfunction "2_2") (pintype "passive"))
      (node (ref "R82") (pin "2") (pinfunction "2_2") (pintype "passive"))
      (node (ref "TR2") (pin "1") (pinfunction "1_1") (pintype "passive"))
    )
    (net (code "15") (name "/TEMP_W") (class "Default")
      (node (ref "C64") (pin "2") (pinfunction "2_2") (pintype "passive"))
      (node (ref "R101") (pin "2") (pinfunction "2_2") (pintype "passive"))
      (node (ref "TR3") (pin "1") (pinfunction "1_1") (pintype "passive"))
    )
    (net (code "16") (name "/VSENSE") (class "Default")
      (node (ref "R57") (pin "1") (pinfunction "1_1") (pintype "passive"))
      (node (ref "R62") (pin "2") (pinfunction "2_2") (pintype "passive"))
    )
    (net (code "17") (name "/VSENSE_U") (class "Default")
      (node (ref "R53") (pin "1") (pinfunction "1_1") (pintype "passive"))
      (node (ref "R55") (pin "2") (pinfunction "2_2") (pintype "passive"))
    )
    (net (code "18") (name "/VSENSE_V") (class "Default")
      (node (ref "R74") (pin "1") (pinfunction "1_1") (pintype "passive"))
      (node (ref "R76") (pin "2") (pinfunction "2_2") (pintype "passive"))
    )
    (net (code "19") (name "/VSENSE_W") (class "Default")
      (node (ref "R93") (pin "1") (pinfunction "1_1") (pintype "passive"))
      (node (ref "R95") (pin "2") (pinfunction "2_2") (pintype "passive"))
    )
    (net (code "20") (name "GND") (class "Default")
      (node (ref "C41") (pin "1") (pinfunction "1_1") (pintype "passive"))
      (node (ref "C42") (pin "1") (pinfunction "1_1") (pintype "passive"))
      (node (ref "C43") (pin "1") (pinfunction "1_1") (pintype "passive"))
      (node (ref "C46") (pin "1") (pinfunction "1_1") (pintype "passive"))
      (node (ref "C52") (pin "1") (pinfunction "1_1") (pintype "passive"))
      (node (ref "C53") (pin "1") (pinfunction "1_1") (pintype "passive"))
      (node (ref "C54") (pin "1") (pinfunction "1_1") (pintype "passive"))
      (node (ref "C55") (pin "1") (pinfunction "1_1") (pintype "passive"))
      (node (ref "C63") (pin "1") (pinfunction "1_1") (pintype "passive"))
      (node (ref "C64") (pin "1") (pinfunction "1_1") (pintype "passive"))
      (node (ref "C65") (pin "1") (pinfunction "1_1") (pintype "passive"))
      (node (ref "C66") (pin "1") (pinfunction "1_1") (pintype "passive"))
      (node (ref "R101") (pin "1") (pinfunction "1_1") (pintype "passive"))
      (node (ref "R56") (pin "1") (pinfunction "1_1") (pintype "passive"))
      (node (ref "R62") (pin "1") (pinfunction "1_1") (pintype "passive"))
      (node (ref "R63") (pin "1") (pinfunction "1_1") (pintype "passive"))
      (node (ref "R77") (pin "1") (pinfunction "1_1") (pintype "passive"))
      (node (ref "R82") (pin "1") (pinfunction "1_1") (pintype "passive"))
      (node (ref "R96") (pin "1") (pinfunction "1_1") (pintype "passive"))
      (node (ref "U13") (pin "4") (pinfunction "GND_4") (pintype "passive"))
      (node (ref "U14") (pin "4") (pinfunction "GND_4") (pintype "passive"))
      (node (ref "U15") (pin "4") (pinfunction "GND_4") (pintype "passive"))
    )
    (net (code "21") (name "Net-(C38-Pad2)") (class "Default")
      (node (ref "C38") (pin "2") (pinfunction "2_2") (pintype "passive"))
      (node (ref "C39") (pin "2") (pinfunction "2_2") (pintype "passive"))
      (node (ref "C40") (pin "2") (pinfunction "2_2") (pintype "passive"))
      (node (ref "R48") (pin "2") (pinfunction "2_2") (pintype "passive"))
      (node (ref "R49") (pin "2") (pinfunction "2_2") (pintype "passive"))
      (node (ref "R50") (pin "2") (pinfunction "2_2") (pintype "passive"))
    )
    (net (code "22") (name "Net-(C49-Pad2)") (class "Default")
      (node (ref "C49") (pin "2") (pinfunction "2_2") (pintype "passive"))
      (node (ref "C50") (pin "2") (pinfunction "2_2") (pintype "passive"))
      (node (ref "C51") (pin "2") (pinfunction "2_2") (pintype "passive"))
      (node (ref "R69") (pin "2") (pinfunction "2_2") (pintype "passive"))
      (node (ref "R70") (pin "2") (pinfunction "2_2") (pintype "passive"))
      (node (ref "R71") (pin "2") (pinfunction "2_2") (pintype "passive"))
    )
    (net (code "23") (name "Net-(C60-Pad2)") (class "Default")
      (node (ref "C60") (pin "2") (pinfunction "2_2") (pintype "passive"))
      (node (ref "C61") (pin "2") (pinfunction "2_2") (pintype "passive"))
      (node (ref "C62") (pin "2") (pinfunction "2_2") (pintype "passive"))
      (node (ref "R88") (pin "2") (pinfunction "2_2") (pintype "passive"))
      (node (ref "R89") (pin "2") (pinfunction "2_2") (pintype "passive"))
      (node (ref "R90") (pin "2") (pinfunction "2_2") (pintype "passive"))
    )
    (net (code "24") (name "Net-(D1-K)") (class "Default")
      (node (ref "C36") (pin "2") (pinfunction "2_2") (pintype "passive"))
      (node (ref "C37") (pin "2") (pinfunction "2_2") (pintype "passive"))
      (node (ref "D1") (pin "C") (pinfunction "K_C") (pintype "passive"))
      (node (ref "U13") (pin "16") (pinfunction "VDDA_16") (pintype "passive"))
    )
    (net (code "25") (name "Net-(D1-PadA)") (class "Default")
      (node (ref "D1") (pin "A") (pinfunction "A_A") (pintype "passive"))
      (node (ref "R43") (pin "2") (pinfunction "2_2") (pintype "passive"))
    )
    (net (code "26") (name "Net-(D2-K)") (class "Default")
      (node (ref "C47") (pin "2") (pinfunction "2_2") (pintype "passive"))
      (node (ref "C48") (pin "2") (pinfunction "2_2") (pintype "passive"))
      (node (ref "D2") (pin "C") (pinfunction "K_C") (pintype "passive"))
      (node (ref "U14") (pin "16") (pinfunction "VDDA_16") (pintype "passive"))
    )
    (net (code "27") (name "Net-(D2-PadA)") (class "Default")
      (node (ref "D2") (pin "A") (pinfunction "A_A") (pintype "passive"))
      (node (ref "R64") (pin "2") (pinfunction "2_2") (pintype "passive"))
    )
    (net (code "28") (name "Net-(D3-K)") (class "Default")
      (node (ref "C58") (pin "2") (pinfunction "2_2") (pintype "passive"))
      (node (ref "C59") (pin "2") (pinfunction "2_2") (pintype "passive"))
      (node (ref "D3") (pin "C") (pinfunction "K_C") (pintype "passive"))
      (node (ref "U15") (pin "16") (pinfunction "VDDA_16") (pintype "passive"))
    )
    (net (code "29") (name "Net-(D3-PadA)") (class "Default")
      (node (ref "D3") (pin "A") (pinfunction "A_A") (pintype "passive"))
      (node (ref "R83") (pin "2") (pinfunction "2_2") (pintype "passive"))
    )
    (net (code "30") (name "Net-(Q1-G)") (class "Default")
      (node (ref "Q1") (pin "1") (pinfunction "G_1") (pintype "passive"))
      (node (ref "R45") (pin "1") (pinfunction "1_1") (pintype "passive"))
    )
    (net (code "31") (name "Net-(Q2-G)") (class "Default")
      (node (ref "Q2") (pin "1") (pinfunction "G_1") (pintype "passive"))
      (node (ref "R47") (pin "1") (pinfunction "1_1") (pintype "passive"))
    )
    (net (code "32") (name "Net-(Q3-G)") (class "Default")
      (node (ref "Q3") (pin "1") (pinfunction "G_1") (pintype "passive"))
      (node (ref "R44") (pin "1") (pinfunction "1_1") (pintype "passive"))
    )
    (net (code "33") (name "Net-(Q4-G)") (class "Default")
      (node (ref "Q4") (pin "1") (pinfunction "G_1") (pintype "passive"))
      (node (ref "R46") (pin "1") (pinfunction "1_1") (pintype "passive"))
    )
    (net (code "34") (name "Net-(Q5-G)") (class "Default")
      (node (ref "Q5") (pin "1") (pinfunction "G_1") (pintype "passive"))
      (node (ref "R58") (pin "2") (pinfunction "2_2") (pintype "passive"))
    )
    (net (code "35") (name "Net-(Q6-G)") (class "Default")
      (node (ref "Q6") (pin "1") (pinfunction "G_1") (pintype "passive"))
      (node (ref "R59") (pin "2") (pinfunction "2_2") (pintype "passive"))
    )
    (net (code "36") (name "Net-(Q7-G)") (class "Default")
      (node (ref "Q7") (pin "1") (pinfunction "G_1") (pintype "passive"))
      (node (ref "R60") (pin "2") (pinfunction "2_2") (pintype "passive"))
    )
    (net (code "37") (name "Net-(Q8-G)") (class "Default")
      (node (ref "Q8") (pin "1") (pinfunction "G_1") (pintype "passive"))
      (node (ref "R61") (pin "2") (pinfunction "2_2") (pintype "passive"))
    )
    (net (code "38") (name "Net-(Q9-G)") (class "Default")
      (node (ref "Q9") (pin "1") (pinfunction "G_1") (pintype "passive"))
      (node (ref "R66") (pin "1") (pinfunction "1_1") (pintype "passive"))
    )
    (net (code "39") (name "Net-(Q10-G)") (class "Default")
      (node (ref "Q10") (pin "1") (pinfunction "G_1") (pintype "passive"))
      (node (ref "R68") (pin "1") (pinfunction "1_1") (pintype "passive"))
    )
    (net (code "40") (name "Net-(Q11-G)") (class "Default")
      (node (ref "Q11") (pin "1") (pinfunction "G_1") (pintype "passive"))
      (node (ref "R65") (pin "1") (pinfunction "1_1") (pintype "passive"))
    )
    (net (code "41") (name "Net-(Q12-G)") (class "Default")
      (node (ref "Q12") (pin "1") (pinfunction "G_1") (pintype "passive"))
      (node (ref "R67") (pin "1") (pinfunction "1_1") (pintype "passive"))
    )
    (net (code "42") (name "Net-(Q13-G)") (class "Default")
      (node (ref "Q13") (pin "1") (pinfunction "G_1") (pintype "passive"))
      (node (ref "R78") (pin "2") (pinfunction "2_2") (pintype "passive"))
    )
    (net (code "43") (name "Net-(Q14-G)") (class "Default")
      (node (ref "Q14") (pin "1") (pinfunction "G_1") (pintype "passive"))
      (node (ref "R79") (pin "2") (pinfunction "2_2") (pintype "passive"))
    )
    (net (code "44") (name "Net-(Q15-G)") (class "Default")
      (node (ref "Q15") (pin "1") (pinfunction "G_1") (pintype "passive"))
      (node (ref "R80") (pin "2") (pinfunction "2_2") (pintype "passive"))
    )
    (net (code "45") (name "Net-(Q16-G)") (class "Default")
      (node (ref "Q16") (pin "1") (pinfunction "G_1") (pintype "passive"))
      (node (ref "R81") (pin "2") (pinfunction "2_2") (pintype "passive"))
    )
    (net (code "46") (name "Net-(Q17-G)") (class "Default")
      (node (ref "Q17") (pin "1") (pinfunction "G_1") (pintype "passive"))
      (node (ref "R85") (pin "1") (pinfunction "1_1") (pintype "passive"))
    )
    (net (code "47") (name "Net-(Q18-G)") (class "Default")
      (node (ref "Q18") (pin "1") (pinfunction "G_1") (pintype "passive"))
      (node (ref "R87") (pin "1") (pinfunction "1_1") (pintype "passive"))
    )
    (net (code "48") (name "Net-(Q19-G)") (class "Default")
      (node (ref "Q19") (pin "1") (pinfunction "G_1") (pintype "passive"))
      (node (ref "R84") (pin "1") (pinfunction "1_1") (pintype "passive"))
    )
    (net (code "49") (name "Net-(Q20-G)") (class "Default")
      (node (ref "Q20") (pin "1") (pinfunction "G_1") (pintype "passive"))
      (node (ref "R86") (pin "1") (pinfunction "1_1") (pintype "passive"))
    )
    (net (code "50") (name "Net-(Q21-G)") (class "Default")
      (node (ref "Q21") (pin "1") (pinfunction "G_1") (pintype "passive"))
      (node (ref "R97") (pin "2") (pinfunction "2_2") (pintype "passive"))
    )
    (net (code "51") (name "Net-(Q22-G)") (class "Default")
      (node (ref "Q22") (pin "1") (pinfunction "G_1") (pintype "passive"))
      (node (ref "R98") (pin "2") (pinfunction "2_2") (pintype "passive"))
    )
    (net (code "52") (name "Net-(Q23-G)") (class "Default")
      (node (ref "Q23") (pin "1") (pinfunction "G_1") (pintype "passive"))
      (node (ref "R99") (pin "2") (pinfunction "2_2") (pintype "passive"))
    )
    (net (code "53") (name "Net-(Q24-G)") (class "Default")
      (node (ref "Q24") (pin "1") (pinfunction "G_1") (pintype "passive"))
      (node (ref "R100") (pin "2") (pinfunction "2_2") (pintype "passive"))
    )
    (net (code "54") (name "Net-(U13-DISABLE)") (class "Default")
      (node (ref "C38") (pin "1") (pinfunction "1_1") (pintype "passive"))
      (node (ref "R48") (pin "1") (pinfunction "1_1") (pintype "passive"))
      (node (ref "R54") (pin "2") (pinfunction "2_2") (pintype "passive"))
      (node (ref "U13") (pin "5") (pinfunction "DISABLE_5") (pintype "passive"))
    )
    (net (code "55") (name "Net-(U13-DT)") (class "Default")
      (node (ref "C41") (pin "2") (pinfunction "2_2") (pintype "passive"))
      (node (ref "R56") (pin "2") (pinfunction "2_2") (pintype "passive"))
      (node (ref "U13") (pin "6") (pinfunction "DT_6") (pintype "passive"))
    )
    (net (code "56") (name "Net-(U13-INA)") (class "Default")
      (node (ref "C40") (pin "1") (pinfunction "1_1") (pintype "passive"))
      (node (ref "R50") (pin "1") (pinfunction "1_1") (pintype "passive"))
      (node (ref "R51") (pin "2") (pinfunction "2_2") (pintype "passive"))
      (node (ref "U13") (pin "1") (pinfunction "INA_1") (pintype "passive"))
    )
    (net (code "57") (name "Net-(U13-INB)") (class "Default")
      (node (ref "C39") (pin "1") (pinfunction "1_1") (pintype "passive"))
      (node (ref "R49") (pin "1") (pinfunction "1_1") (pintype "passive"))
      (node (ref "R52") (pin "2") (pinfunction "2_2") (pintype "passive"))
      (node (ref "U13") (pin "2") (pinfunction "INB_2") (pintype "passive"))
    )
    (net (code "58") (name "Net-(U13-OUTA)") (class "Default")
      (node (ref "R44") (pin "2") (pinfunction "2_2") (pintype "passive"))
      (node (ref "R45") (pin "2") (pinfunction "2_2") (pintype "passive"))
      (node (ref "R46") (pin "2") (pinfunction "2_2") (pintype "passive"))
      (node (ref "R47") (pin "2") (pinfunction "2_2") (pintype "passive"))
      (node (ref "U13") (pin "15") (pinfunction "OUTA_15") (pintype "passive"))
    )
    (net (code "59") (name "Net-(U13-OUTB)") (class "Default")
      (node (ref "R58") (pin "1") (pinfunction "1_1") (pintype "passive"))
      (node (ref "R59") (pin "1") (pinfunction "1_1") (pintype "passive"))
      (node (ref "R60") (pin "1") (pinfunction "1_1") (pintype "passive"))
      (node (ref "R61") (pin "1") (pinfunction "1_1") (pintype "passive"))
      (node (ref "U13") (pin "10") (pinfunction "OUTB_10") (pintype "passive"))
    )
    (net (code "60") (name "Net-(U14-DISABLE)") (class "Default")
      (node (ref "C49") (pin "1") (pinfunction "1_1") (pintype "passive"))
      (node (ref "R69") (pin "1") (pinfunction "1_1") (pintype "passive"))
      (node (ref "R75") (pin "2") (pinfunction "2_2") (pintype "passive"))
      (node (ref "U14") (pin "5") (pinfunction "DISABLE_5") (pintype "passive"))
    )
    (net (code "61") (name "Net-(U14-DT)") (class "Default")
      (node (ref "C52") (pin "2") (pinfunction "2_2") (pintype "passive"))
      (node (ref "R77") (pin "2") (pinfunction "2_2") (pintype "passive"))
      (node (ref "U14") (pin "6") (pinfunction "DT_6") (pintype "passive"))
    )
    (net (code "62") (name "Net-(U14-INA)") (class "Default")
      (node (ref "C51") (pin "1") (pinfunction "1_1") (pintype "passive"))
      (node (ref "R71") (pin "1") (pinfunction "1_1") (pintype "passive"))
      (node (ref "R72") (pin "2") (pinfunction "2_2") (pintype "passive"))
      (node (ref "U14") (pin "1") (pinfunction "INA_1") (pintype "passive"))
    )
    (net (code "63") (name "Net-(U14-INB)") (class "Default")
      (node (ref "C50") (pin "1") (pinfunction "1_1") (pintype "passive"))
      (node (ref "R70") (pin "1") (pinfunction "1_1") (pintype "passive"))
      (node (ref "R73") (pin "2") (pinfunction "2_2") (pintype "passive"))
      (node (ref "U14") (pin "2") (pinfunction "INB_2") (pintype "passive"))
    )
    (net (code "64") (name "Net-(U14-OUTA)") (class "Default")
      (node (ref "R65") (pin "2") (pinfunction "2_2") (pintype "passive"))
      (node (ref "R66") (pin "2") (pinfunction "2_2") (pintype "passive"))
      (node (ref "R67") (pin "2") (pinfunction "2_2") (pintype "passive"))
      (node (ref "R68") (pin "2") (pinfunction "2_2") (pintype "passive"))
      (node (ref "U14") (pin "15") (pinfunction "OUTA_15") (pintype "passive"))
    )
    (net (code "65") (name "Net-(U14-OUTB)") (class "Default")
      (node (ref "R78") (pin "1") (pinfunction "1_1") (pintype "passive"))
      (node (ref "R79") (pin "1") (pinfunction "1_1") (pintype "passive"))
      (node (ref "R80") (pin "1") (pinfunction "1_1") (pintype "passive"))
      (node (ref "R81") (pin "1") (pinfunction "1_1") (pintype "passive"))
      (node (ref "U14") (pin "10") (pinfunction "OUTB_10") (pintype "passive"))
    )
    (net (code "66") (name "Net-(U15-DISABLE)") (class "Default")
      (node (ref "C60") (pin "1") (pinfunction "1_1") (pintype "passive"))
      (node (ref "R88") (pin "1") (pinfunction "1_1") (pintype "passive"))
      (node (ref "R94") (pin "2") (pinfunction "2_2") (pintype "passive"))
      (node (ref "U15") (pin "5") (pinfunction "DISABLE_5") (pintype "passive"))
    )
    (net (code "67") (name "Net-(U15-DT)") (class "Default")
      (node (ref "C63") (pin "2") (pinfunction "2_2") (pintype "passive"))
      (node (ref "R96") (pin "2") (pinfunction "2_2") (pintype "passive"))
      (node (ref "U15") (pin "6") (pinfunction "DT_6") (pintype "passive"))
    )
    (net (code "68") (name "Net-(U15-INA)") (class "Default")
      (node (ref "C62") (pin "1") (pinfunction "1_1") (pintype "passive"))
      (node (ref "R90") (pin "1") (pinfunction "1_1") (pintype "passive"))
      (node (ref "R91") (pin "2") (pinfunction "2_2") (pintype "passive"))
      (node (ref "U15") (pin "1") (pinfunction "INA_1") (pintype "passive"))
    )
    (net (code "69") (name "Net-(U15-INB)") (class "Default")
      (node (ref "C61") (pin "1") (pinfunction "1_1") (pintype "passive"))
      (node (ref "R89") (pin "1") (pinfunction "1_1") (pintype "passive"))
      (node (ref "R92") (pin "2") (pinfunction "2_2") (pintype "passive"))
      (node (ref "U15") (pin "2") (pinfunction "INB_2") (pintype "passive"))
    )
    (net (code "70") (name "Net-(U15-OUTA)") (class "Default")
      (node (ref "R84") (pin "2") (pinfunction "2_2") (pintype "passive"))
      (node (ref "R85") (pin "2") (pinfunction "2_2") (pintype "passive"))
      (node (ref "R86") (pin "2") (pinfunction "2_2") (pintype "passive"))
      (node (ref "R87") (pin "2") (pinfunction "2_2") (pintype "passive"))
      (node (ref "U15") (pin "15") (pinfunction "OUTA_15") (pintype "passive"))
    )
    (net (code "71") (name "Net-(U15-OUTB)") (class "Default")
      (node (ref "R100") (pin "1") (pinfunction "1_1") (pintype "passive"))
      (node (ref "R97") (pin "1") (pinfunction "1_1") (pintype "passive"))
      (node (ref "R98") (pin "1") (pinfunction "1_1") (pintype "passive"))
      (node (ref "R99") (pin "1") (pinfunction "1_1") (pintype "passive"))
      (node (ref "U15") (pin "10") (pinfunction "OUTB_10") (pintype "passive"))
    )
    (net (code "72") (name "V+") (class "Default")
      (node (ref "J2") (pin "1") (pinfunction "1_1") (pintype "passive"))
      (node (ref "Q1") (pin "2") (pinfunction "D_2") (pintype "passive"))
      (node (ref "Q10") (pin "2") (pinfunction "D_2") (pintype "passive"))
      (node (ref "Q11") (pin "2") (pinfunction "D_2") (pintype "passive"))
      (node (ref "Q12") (pin "2") (pinfunction "D_2") (pintype "passive"))
      (node (ref "Q17") (pin "2") (pinfunction "D_2") (pintype "passive"))
      (node (ref "Q18") (pin "2") (pinfunction "D_2") (pintype "passive"))
      (node (ref "Q19") (pin "2") (pinfunction "D_2") (pintype "passive"))
      (node (ref "Q2") (pin "2") (pinfunction "D_2") (pintype "passive"))
      (node (ref "Q20") (pin "2") (pinfunction "D_2") (pintype "passive"))
      (node (ref "Q3") (pin "2") (pinfunction "D_2") (pintype "passive"))
      (node (ref "Q4") (pin "2") (pinfunction "D_2") (pintype "passive"))
      (node (ref "Q9") (pin "2") (pinfunction "D_2") (pintype "passive"))
      (node (ref "R57") (pin "2") (pinfunction "2_2") (pintype "passive"))
    )
    (net (code "73") (name "V-") (class "Default")
      (node (ref "C44") (pin "1") (pinfunction "1_1") (pintype "passive"))
      (node (ref "C45") (pin "1") (pinfunction "1_1") (pintype "passive"))
      (node (ref "C56") (pin "1") (pinfunction "1_1") (pintype "passive"))
      (node (ref "C57") (pin "1") (pinfunction "1_1") (pintype "passive"))
      (node (ref "C67") (pin "1") (pinfunction "1_1") (pintype "passive"))
      (node (ref "C68") (pin "1") (pinfunction "1_1") (pintype "passive"))
      (node (ref "J3") (pin "1") (pinfunction "1_1") (pintype "passive"))
      (node (ref "Q13") (pin "3") (pinfunction "S_3") (pintype "passive"))
      (node (ref "Q14") (pin "3") (pinfunction "S_3") (pintype "passive"))
      (node (ref "Q16") (pin "3") (pinfunction "S_3") (pintype "passive"))
      (node (ref "Q21") (pin "3") (pinfunction "S_3") (pintype "passive"))
      (node (ref "Q22") (pin "3") (pinfunction "S_3") (pintype "passive"))
      (node (ref "Q24") (pin "3") (pinfunction "S_3") (pintype "passive"))
      (node (ref "Q5") (pin "3") (pinfunction "S_3") (pintype "passive"))
      (node (ref "Q6") (pin "3") (pinfunction "S_3") (pintype "passive"))
      (node (ref "Q8") (pin "3") (pinfunction "S_3") (pintype "passive"))
      (node (ref "R55") (pin "1") (pinfunction "1_1") (pintype "passive"))
      (node (ref "R76") (pin "1") (pinfunction "1_1") (pintype "passive"))
      (node (ref "R95") (pin "1") (pinfunction "1_1") (pintype "passive"))
      (node (ref "U13") (pin "9") (pinfunction "VSSB_9") (pintype "passive"))
      (node (ref "U14") (pin "9") (pinfunction "VSSB_9") (pintype "passive"))
      (node (ref "U15") (pin "9") (pinfunction "VSSB_9") (pintype "passive"))
    )
    (net (code "74") (name "unconnected-(Q7-D-Pad2)") (class "Default")
      (node (ref "Q7") (pin "2") (pinfunction "D_2") (pintype "passive"))
    )
    (net (code "75") (name "unconnected-(Q7-S-Pad3)") (class "Default")
      (node (ref "Q7") (pin "3") (pinfunction "S_3") (pintype "passive"))
    )
    (net (code "76") (name "unconnected-(Q15-D-Pad2)") (class "Default")
      (node (ref "Q15") (pin "2") (pinfunction "D_2") (pintype "passive"))
    )
    (net (code "77") (name "unconnected-(Q15-S-Pad3)") (class "Default")
      (node (ref "Q15") (pin "3") (pinfunction "S_3") (pintype "passive"))
    )
    (net (code "78") (name "unconnected-(Q23-D-Pad2)") (class "Default")
      (node (ref "Q23") (pin "2") (pinfunction "D_2") (pintype "passive"))
    )
    (net (code "79") (name "unconnected-(Q23-S-Pad3)") (class "Default")
      (node (ref "Q23") (pin "3") (pinfunction "S_3") (pintype "passive"))
    )
    (net (code "80") (name "unconnected-(U13-NC_1-Pad7)") (class "Default")
      (node (ref "U13") (pin "7") (pinfunction "NC_1_7") (pintype "passive"))
    )
    (net (code "81") (name "unconnected-(U13-NC_2-Pad12)") (class "Default")
      (node (ref "U13") (pin "12") (pinfunction "NC_2_12") (pintype "passive"))
    )
    (net (code "82") (name "unconnected-(U13-NC_3-Pad13)") (class "Default")
      (node (ref "U13") (pin "13") (pinfunction "NC_3_13") (pintype "passive"))
    )
    (net (code "83") (name "unconnected-(U14-NC_1-Pad7)") (class "Default")
      (node (ref "U14") (pin "7") (pinfunction "NC_1_7") (pintype "passive"))
    )
    (net (code "84") (name "unconnected-(U14-NC_2-Pad12)") (class "Default")
      (node (ref "U14") (pin "12") (pinfunction "NC_2_12") (pintype "passive"))
    )
    (net (code "85") (name "unconnected-(U14-NC_3-Pad13)") (class "Default")
      (node (ref "U14") (pin "13") (pinfunction "NC_3_13") (pintype "passive"))
    )
    (net (code "86") (name "unconnected-(U15-NC_1-Pad7)") (class "Default")
      (node (ref "U15") (pin "7") (pinfunction "NC_1_7") (pintype "passive"))
    )
    (net (code "87") (name "unconnected-(U15-NC_2-Pad12)") (class "Default")
      (node (ref "U15") (pin "12") (pinfunction "NC_2_12") (pintype "passive"))
    )
    (net (code "88") (name "unconnected-(U15-NC_3-Pad13)") (class "Default")
      (node (ref "U15") (pin "13") (pinfunction "NC_3_13") (pintype "passive"))
    )
  )
)
